# keypad.net
KiCad netlist of a schematic drawn in EAGLE
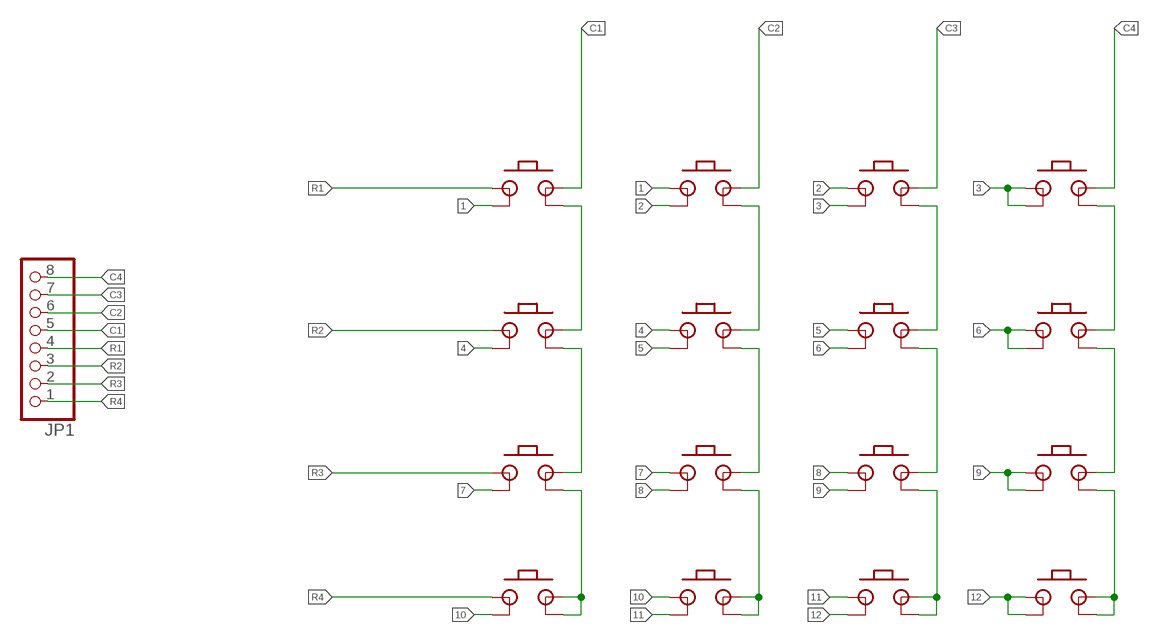
[diagram p0: schematic, sheet 1]

(export (version "E")
  (design (tool "Eeschema 10.0.6"))
  (components
    (comp (ref "JP1")
      (value "PINHD-1X8")
      (footprint "eagle-import:1X08")
      (libsource (lib "eagle-import") (part "PINHD-1X8"))
    )
    (comp (ref "PB1")
      (value "TACTSW")
      (footprint "eagle-import:TACTSW")
      (libsource (lib "eagle-import") (part "TACTSW"))
    )
    (comp (ref "PB2")
      (value "TACTSW")
      (footprint "eagle-import:TACTSW")
      (libsource (lib "eagle-import") (part "TACTSW"))
    )
    (comp (ref "PB3")
      (value "TACTSW")
      (footprint "eagle-import:TACTSW")
      (libsource (lib "eagle-import") (part "TACTSW"))
    )
    (comp (ref "PB4")
      (value "TACTSW")
      (footprint "eagle-import:TACTSW")
      (libsource (lib "eagle-import") (part "TACTSW"))
    )
    (comp (ref "PB5")
      (value "TACTSW")
      (footprint "eagle-import:TACTSW")
      (libsource (lib "eagle-import") (part "TACTSW"))
    )
    (comp (ref "PB6")
      (value "TACTSW")
      (footprint "eagle-import:TACTSW")
      (libsource (lib "eagle-import") (part "TACTSW"))
    )
    (comp (ref "PB7")
      (value "TACTSW")
      (footprint "eagle-import:TACTSW")
      (libsource (lib "eagle-import") (part "TACTSW"))
    )
    (comp (ref "PB8")
      (value "TACTSW")
      (footprint "eagle-import:TACTSW")
      (libsource (lib "eagle-import") (part "TACTSW"))
    )
    (comp (ref "PB9")
      (value "TACTSW")
      (footprint "eagle-import:TACTSW")
      (libsource (lib "eagle-import") (part "TACTSW"))
    )
    (comp (ref "PB10")
      (value "TACTSW")
      (footprint "eagle-import:TACTSW")
      (libsource (lib "eagle-import") (part "TACTSW"))
    )
    (comp (ref "PB11")
      (value "TACTSW")
      (footprint "eagle-import:TACTSW")
      (libsource (lib "eagle-import") (part "TACTSW"))
    )
    (comp (ref "PB12")
      (value "TACTSW")
      (footprint "eagle-import:TACTSW")
      (libsource (lib "eagle-import") (part "TACTSW"))
    )
    (comp (ref "PB13")
      (value "TACTSW")
      (footprint "eagle-import:TACTSW")
      (libsource (lib "eagle-import") (part "TACTSW"))
    )
    (comp (ref "PB14")
      (value "TACTSW")
      (footprint "eagle-import:TACTSW")
      (libsource (lib "eagle-import") (part "TACTSW"))
    )
    (comp (ref "PB15")
      (value "TACTSW")
      (footprint "eagle-import:TACTSW")
      (libsource (lib "eagle-import") (part "TACTSW"))
    )
    (comp (ref "PB16")
      (value "TACTSW")
      (footprint "eagle-import:TACTSW")
      (libsource (lib "eagle-import") (part "TACTSW"))
    )
  )
  (nets
    (net (code "1") (name "1") (class "Default")
      (node (ref "PB1") (pin "P$2") (pinfunction "P$3_P$2") (pintype "passive"))
      (node (ref "PB2") (pin "P$1") (pinfunction "P$1_P$1") (pintype "passive"))
    )
    (net (code "2") (name "2") (class "Default")
      (node (ref "PB2") (pin "P$2") (pinfunction "P$3_P$2") (pintype "passive"))
      (node (ref "PB3") (pin "P$1") (pinfunction "P$1_P$1") (pintype "passive"))
    )
    (net (code "3") (name "3") (class "Default")
      (node (ref "PB3") (pin "P$2") (pinfunction "P$3_P$2") (pintype "passive"))
      (node (ref "PB4") (pin "P$1") (pinfunction "P$1_P$1") (pintype "passive"))
      (node (ref "PB4") (pin "P$2") (pinfunction "P$3_P$2") (pintype "passive"))
    )
    (net (code "4") (name "4") (class "Default")
      (node (ref "PB5") (pin "P$2") (pinfunction "P$3_P$2") (pintype "passive"))
      (node (ref "PB6") (pin "P$1") (pinfunction "P$1_P$1") (pintype "passive"))
    )
    (net (code "5") (name "5") (class "Default")
      (node (ref "PB6") (pin "P$2") (pinfunction "P$3_P$2") (pintype "passive"))
      (node (ref "PB7") (pin "P$1") (pinfunction "P$1_P$1") (pintype "passive"))
    )
    (net (code "6") (name "6") (class "Default")
      (node (ref "PB7") (pin "P$2") (pinfunction "P$3_P$2") (pintype "passive"))
      (node (ref "PB8") (pin "P$1") (pinfunction "P$1_P$1") (pintype "passive"))
      (node (ref "PB8") (pin "P$2") (pinfunction "P$3_P$2") (pintype "passive"))
    )
    (net (code "7") (name "7") (class "Default")
      (node (ref "PB10") (pin "P$1") (pinfunction "P$1_P$1") (pintype "passive"))
      (node (ref "PB9") (pin "P$2") (pinfunction "P$3_P$2") (pintype "passive"))
    )
    (net (code "8") (name "8") (class "Default")
      (node (ref "PB10") (pin "P$2") (pinfunction "P$3_P$2") (pintype "passive"))
      (node (ref "PB11") (pin "P$1") (pinfunction "P$1_P$1") (pintype "passive"))
    )
    (net (code "9") (name "9") (class "Default")
      (node (ref "PB11") (pin "P$2") (pinfunction "P$3_P$2") (pintype "passive"))
      (node (ref "PB11") (pin "P$3") (pinfunction "P$2_P$3") (pintype "passive"))
      (node (ref "PB12") (pin "P$1") (pinfunction "P$1_P$1") (pintype "passive"))
      (node (ref "PB12") (pin "P$2") (pinfunction "P$3_P$2") (pintype "passive"))
      (node (ref "PB7") (pin "P$4") (pinfunction "P$4_P$4") (pintype "passive"))
    )
    (net (code "10") (name "10") (class "Default")
      (node (ref "PB13") (pin "P$2") (pinfunction "P$3_P$2") (pintype "passive"))
      (node (ref "PB14") (pin "P$1") (pinfunction "P$1_P$1") (pintype "passive"))
    )
    (net (code "11") (name "11") (class "Default")
      (node (ref "PB14") (pin "P$2") (pinfunction "P$3_P$2") (pintype "passive"))
      (node (ref "PB15") (pin "P$1") (pinfunction "P$1_P$1") (pintype "passive"))
    )
    (net (code "12") (name "12") (class "Default")
      (node (ref "PB15") (pin "P$2") (pinfunction "P$3_P$2") (pintype "passive"))
      (node (ref "PB16") (pin "P$1") (pinfunction "P$1_P$1") (pintype "passive"))
      (node (ref "PB16") (pin "P$2") (pinfunction "P$3_P$2") (pintype "passive"))
    )
    (net (code "13") (name "C1") (class "Default")
      (node (ref "JP1") (pin "5") (pinfunction "5_5") (pintype "passive"))
      (node (ref "PB1") (pin "P$3") (pinfunction "P$2_P$3") (pintype "passive"))
    )
    (net (code "14") (name "C2") (class "Default")
      (node (ref "JP1") (pin "6") (pinfunction "6_6") (pintype "passive"))
      (node (ref "PB2") (pin "P$3") (pinfunction "P$2_P$3") (pintype "passive"))
    )
    (net (code "15") (name "C3") (class "Default")
      (node (ref "JP1") (pin "7") (pinfunction "7_7") (pintype "passive"))
      (node (ref "PB3") (pin "P$3") (pinfunction "P$2_P$3") (pintype "passive"))
    )
    (net (code "16") (name "C4") (class "Default")
      (node (ref "JP1") (pin "8") (pinfunction "8_8") (pintype "passive"))
      (node (ref "PB4") (pin "P$3") (pinfunction "P$2_P$3") (pintype "passive"))
    )
    (net (code "17") (name "Net-(PB5-P$2)") (class "Default")
      (node (ref "PB1") (pin "P$4") (pinfunction "P$4_P$4") (pintype "passive"))
      (node (ref "PB5") (pin "P$3") (pinfunction "P$2_P$3") (pintype "passive"))
    )
    (net (code "18") (name "Net-(PB6-P$2)") (class "Default")
      (node (ref "PB2") (pin "P$4") (pinfunction "P$4_P$4") (pintype "passive"))
      (node (ref "PB6") (pin "P$3") (pinfunction "P$2_P$3") (pintype "passive"))
    )
    (net (code "19") (name "Net-(PB7-P$2)") (class "Default")
      (node (ref "PB3") (pin "P$4") (pinfunction "P$4_P$4") (pintype "passive"))
      (node (ref "PB7") (pin "P$3") (pinfunction "P$2_P$3") (pintype "passive"))
    )
    (net (code "20") (name "Net-(PB8-P$2)") (class "Default")
      (node (ref "PB4") (pin "P$4") (pinfunction "P$4_P$4") (pintype "passive"))
      (node (ref "PB8") (pin "P$3") (pinfunction "P$2_P$3") (pintype "passive"))
    )
    (net (code "21") (name "Net-(PB9-P$2)") (class "Default")
      (node (ref "PB5") (pin "P$4") (pinfunction "P$4_P$4") (pintype "passive"))
      (node (ref "PB9") (pin "P$3") (pinfunction "P$2_P$3") (pintype "passive"))
    )
    (net (code "22") (name "Net-(PB10-P$2)") (class "Default")
      (node (ref "PB10") (pin "P$3") (pinfunction "P$2_P$3") (pintype "passive"))
      (node (ref "PB6") (pin "P$4") (pinfunction "P$4_P$4") (pintype "passive"))
    )
    (net (code "23") (name "Net-(PB12-P$2)") (class "Default")
      (node (ref "PB12") (pin "P$3") (pinfunction "P$2_P$3") (pintype "passive"))
      (node (ref "PB8") (pin "P$4") (pinfunction "P$4_P$4") (pintype "passive"))
    )
    (net (code "24") (name "Net-(PB13-P$2)") (class "Default")
      (node (ref "PB13") (pin "P$3") (pinfunction "P$2_P$3") (pintype "passive"))
      (node (ref "PB13") (pin "P$4") (pinfunction "P$4_P$4") (pintype "passive"))
      (node (ref "PB9") (pin "P$4") (pinfunction "P$4_P$4") (pintype "passive"))
    )
    (net (code "25") (name "Net-(PB14-P$2)") (class "Default")
      (node (ref "PB10") (pin "P$4") (pinfunction "P$4_P$4") (pintype "passive"))
      (node (ref "PB14") (pin "P$3") (pinfunction "P$2_P$3") (pintype "passive"))
      (node (ref "PB14") (pin "P$4") (pinfunction "P$4_P$4") (pintype "passive"))
    )
    (net (code "26") (name "Net-(PB15-P$2)") (class "Default")
      (node (ref "PB11") (pin "P$4") (pinfunction "P$4_P$4") (pintype "passive"))
      (node (ref "PB15") (pin "P$3") (pinfunction "P$2_P$3") (pintype "passive"))
      (node (ref "PB15") (pin "P$4") (pinfunction "P$4_P$4") (pintype "passive"))
    )
    (net (code "27") (name "Net-(PB16-P$2)") (class "Default")
      (node (ref "PB12") (pin "P$4") (pinfunction "P$4_P$4") (pintype "passive"))
      (node (ref "PB16") (pin "P$3") (pinfunction "P$2_P$3") (pintype "passive"))
      (node (ref "PB16") (pin "P$4") (pinfunction "P$4_P$4") (pintype "passive"))
    )
    (net (code "28") (name "R1") (class "Default")
      (node (ref "JP1") (pin "4") (pinfunction "4_4") (pintype "passive"))
      (node (ref "PB1") (pin "P$1") (pinfunction "P$1_P$1") (pintype "passive"))
    )
    (net (code "29") (name "R2") (class "Default")
      (node (ref "JP1") (pin "3") (pinfunction "3_3") (pintype "passive"))
      (node (ref "PB5") (pin "P$1") (pinfunction "P$1_P$1") (pintype "passive"))
    )
    (net (code "30") (name "R3") (class "Default")
      (node (ref "JP1") (pin "2") (pinfunction "2_2") (pintype "passive"))
      (node (ref "PB9") (pin "P$1") (pinfunction "P$1_P$1") (pintype "passive"))
    )
    (net (code "31") (name "R4") (class "Default")
      (node (ref "JP1") (pin "1") (pinfunction "1_1") (pintype "passive"))
      (node (ref "PB13") (pin "P$1") (pinfunction "P$1_P$1") (pintype "passive"))
    )
  )
)
